# LowFreqSignal_V2.net
KiCad netlist of a schematic drawn in Altium Designer
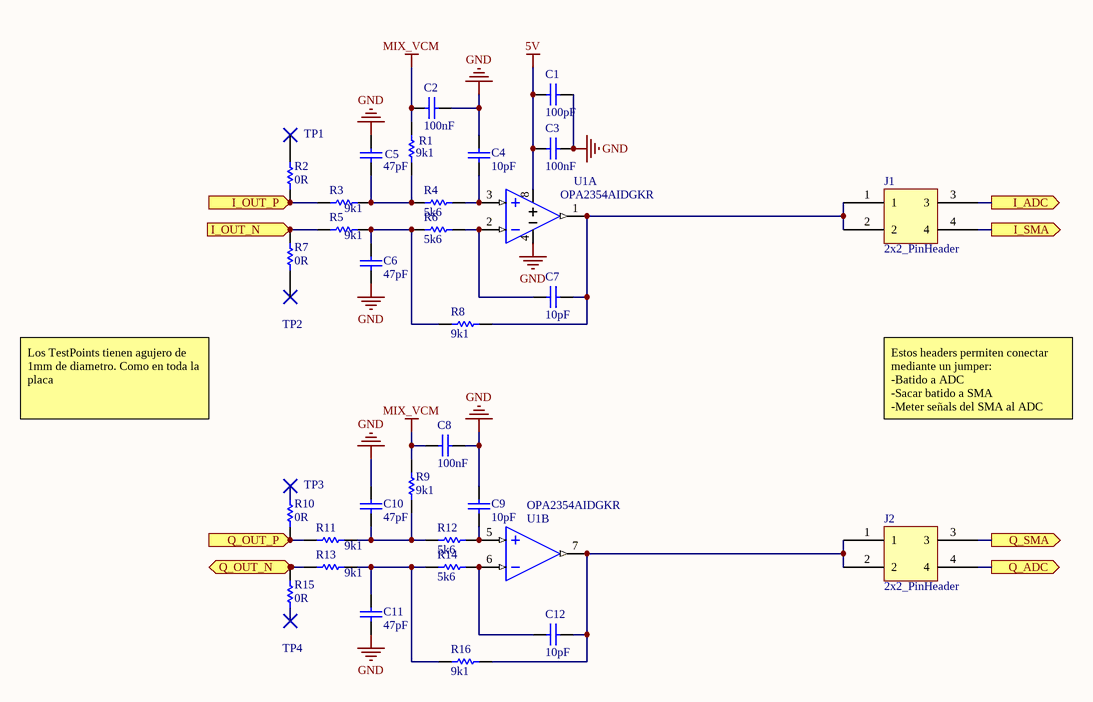
[diagram p0: LowFreqSignal_V2.SchDoc]

(export (version "E")
  (design (tool "Eeschema 10.0.6"))
  (components
    (comp (ref "C1")
      (value "100pF")
      (footprint "0603 Cap")
      (description "CAP CER 100PF 50V X7R 0603")
      (fields
        (field (name "MANUFACTURER") "Samsung Electro-Mechanics America, Inc.")
        (field (name "MANUFACTURER PART NUMBER") "CL10B101KB8NNNC")
      )
      (libsource (lib "Componentes_base") (part "CL10B101KB8NNNC"))
    )
    (comp (ref "C2")
      (value "100nF")
      (footprint "0603 Cap")
      (description "CAP CER 0.1UF 16V X7R 0603")
      (fields
        (field (name "MANUFACTURER") "KEMET")
        (field (name "MANUFACTURER PART NUMBER") "C0603C104K4RACTU")
      )
      (libsource (lib "Componentes_base") (part "C0603C104K4RACTU"))
    )
    (comp (ref "C3")
      (value "100nF")
      (footprint "0603 Cap")
      (description "CAP CER 0.1UF 16V X7R 0603")
      (fields
        (field (name "MANUFACTURER") "KEMET")
        (field (name "MANUFACTURER PART NUMBER") "C0603C104K4RACTU")
      )
      (libsource (lib "Componentes_base") (part "C0603C104K4RACTU"))
    )
    (comp (ref "C4")
      (value "10pF")
      (footprint "0603 Cap")
      (description "CAP CER 16V X7R 0603")
      (fields (field (name "TOLERANCE") "10") (field (name "VOLTAGE") "16"))
      (libsource (lib "Componentes_base") (part "C_0603"))
    )
    (comp (ref "C5")
      (value "47pF")
      (footprint "0603 Cap")
      (description "CAP CER 16V X7R 0603")
      (fields (field (name "TOLERANCE") "10") (field (name "VOLTAGE") "16"))
      (libsource (lib "Componentes_base") (part "C_0603"))
    )
    (comp (ref "C6")
      (value "47pF")
      (footprint "0603 Cap")
      (description "CAP CER 16V X7R 0603")
      (fields (field (name "TOLERANCE") "10") (field (name "VOLTAGE") "16"))
      (libsource (lib "Componentes_base") (part "C_0603"))
    )
    (comp (ref "C7")
      (value "10pF")
      (footprint "0603 Cap")
      (description "CAP CER 16V X7R 0603")
      (fields (field (name "TOLERANCE") "10") (field (name "VOLTAGE") "16"))
      (libsource (lib "Componentes_base") (part "C_0603"))
    )
    (comp (ref "C8")
      (value "100nF")
      (footprint "0603 Cap")
      (description "CAP CER 0.1UF 16V X7R 0603")
      (fields
        (field (name "MANUFACTURER") "KEMET")
        (field (name "MANUFACTURER PART NUMBER") "C0603C104K4RACTU")
      )
      (libsource (lib "Componentes_base") (part "C0603C104K4RACTU"))
    )
    (comp (ref "C9")
      (value "10pF")
      (footprint "0603 Cap")
      (description "CAP CER 16V X7R 0603")
      (fields (field (name "TOLERANCE") "10") (field (name "VOLTAGE") "16"))
      (libsource (lib "Componentes_base") (part "C_0603"))
    )
    (comp (ref "C10")
      (value "47pF")
      (footprint "0603 Cap")
      (description "CAP CER 16V X7R 0603")
      (fields (field (name "TOLERANCE") "10") (field (name "VOLTAGE") "16"))
      (libsource (lib "Componentes_base") (part "C_0603"))
    )
    (comp (ref "C11")
      (value "47pF")
      (footprint "0603 Cap")
      (description "CAP CER 16V X7R 0603")
      (fields (field (name "TOLERANCE") "10") (field (name "VOLTAGE") "16"))
      (libsource (lib "Componentes_base") (part "C_0603"))
    )
    (comp (ref "C12")
      (value "10pF")
      (footprint "0603 Cap")
      (description "CAP CER 16V X7R 0603")
      (fields (field (name "TOLERANCE") "10") (field (name "VOLTAGE") "16"))
      (libsource (lib "Componentes_base") (part "C_0603"))
    )
    (comp (ref "J1")
      (value "2x2_PinHeader")
      (footprint "2x2_PinHeader")
      (libsource (lib "Schlib1") (part "2x2_PinHeader"))
    )
    (comp (ref "J2")
      (value "2x2_PinHeader")
      (footprint "2x2_PinHeader")
      (libsource (lib "Schlib1") (part "2x2_PinHeader"))
    )
    (comp (ref "R1")
      (value "9k1")
      (footprint "0603 Res")
      (description "SMD Resistor, 1%, 0.1W, 0603")
      (fields (field (name "TOLERANCE") "1"))
      (libsource (lib "Componentes_base") (part "R_0603"))
    )
    (comp (ref "R2")
      (value "0R")
      (footprint "0603 Res")
      (description "SMD Resistor, 1%, 0.1W, 0603")
      (fields (field (name "TOLERANCE") "1"))
      (libsource (lib "Componentes_base") (part "R_0603"))
    )
    (comp (ref "R3")
      (value "9k1")
      (footprint "0603 Res")
      (description "SMD Resistor, 1%, 0.1W, 0603")
      (fields (field (name "TOLERANCE") "1"))
      (libsource (lib "Componentes_base") (part "R_0603"))
    )
    (comp (ref "R4")
      (value "5k6")
      (footprint "0603 Res")
      (description "SMD Resistor, 1%, 0.1W, 0603")
      (fields (field (name "TOLERANCE") "1"))
      (libsource (lib "Componentes_base") (part "R_0603"))
    )
    (comp (ref "R5")
      (value "9k1")
      (footprint "0603 Res")
      (description "SMD Resistor, 1%, 0.1W, 0603")
      (fields (field (name "TOLERANCE") "1"))
      (libsource (lib "Componentes_base") (part "R_0603"))
    )
    (comp (ref "R6")
      (value "5k6")
      (footprint "0603 Res")
      (description "SMD Resistor, 1%, 0.1W, 0603")
      (fields (field (name "TOLERANCE") "1"))
      (libsource (lib "Componentes_base") (part "R_0603"))
    )
    (comp (ref "R7")
      (value "0R")
      (footprint "0603 Res")
      (description "SMD Resistor, 1%, 0.1W, 0603")
      (fields (field (name "TOLERANCE") "1"))
      (libsource (lib "Componentes_base") (part "R_0603"))
    )
    (comp (ref "R8")
      (value "9k1")
      (footprint "0603 Res")
      (description "SMD Resistor, 1%, 0.1W, 0603")
      (fields (field (name "TOLERANCE") "1"))
      (libsource (lib "Componentes_base") (part "R_0603"))
    )
    (comp (ref "R9")
      (value "9k1")
      (footprint "0603 Res")
      (description "SMD Resistor, 1%, 0.1W, 0603")
      (fields (field (name "TOLERANCE") "1"))
      (libsource (lib "Componentes_base") (part "R_0603"))
    )
    (comp (ref "R10")
      (value "0R")
      (footprint "0603 Res")
      (description "SMD Resistor, 1%, 0.1W, 0603")
      (fields (field (name "TOLERANCE") "1"))
      (libsource (lib "Componentes_base") (part "R_0603"))
    )
    (comp (ref "R11")
      (value "9k1")
      (footprint "0603 Res")
      (description "SMD Resistor, 1%, 0.1W, 0603")
      (fields (field (name "TOLERANCE") "1"))
      (libsource (lib "Componentes_base") (part "R_0603"))
    )
    (comp (ref "R12")
      (value "5k6")
      (footprint "0603 Res")
      (description "SMD Resistor, 1%, 0.1W, 0603")
      (fields (field (name "TOLERANCE") "1"))
      (libsource (lib "Componentes_base") (part "R_0603"))
    )
    (comp (ref "R13")
      (value "9k1")
      (footprint "0603 Res")
      (description "SMD Resistor, 1%, 0.1W, 0603")
      (fields (field (name "TOLERANCE") "1"))
      (libsource (lib "Componentes_base") (part "R_0603"))
    )
    (comp (ref "R14")
      (value "5k6")
      (footprint "0603 Res")
      (description "SMD Resistor, 1%, 0.1W, 0603")
      (fields (field (name "TOLERANCE") "1"))
      (libsource (lib "Componentes_base") (part "R_0603"))
    )
    (comp (ref "R15")
      (value "0R")
      (footprint "0603 Res")
      (description "SMD Resistor, 1%, 0.1W, 0603")
      (fields (field (name "TOLERANCE") "1"))
      (libsource (lib "Componentes_base") (part "R_0603"))
    )
    (comp (ref "R16")
      (value "9k1")
      (footprint "0603 Res")
      (description "SMD Resistor, 1%, 0.1W, 0603")
      (fields (field (name "TOLERANCE") "1"))
      (libsource (lib "Componentes_base") (part "R_0603"))
    )
    (comp (ref "TP1")
      (value "TEST_POINT_PIN")
      (footprint "TESTPOINT")
      (description "Test point for single pin")
      (libsource (lib "Componentes_base") (part "TEST_POINT_PIN"))
    )
    (comp (ref "TP2")
      (value "TEST_POINT_PIN")
      (footprint "TESTPOINT")
      (description "Test point for single pin")
      (libsource (lib "Componentes_base") (part "TEST_POINT_PIN"))
    )
    (comp (ref "TP3")
      (value "TEST_POINT_PIN")
      (footprint "TESTPOINT")
      (description "Test point for single pin")
      (libsource (lib "Componentes_base") (part "TEST_POINT_PIN"))
    )
    (comp (ref "TP4")
      (value "TEST_POINT_PIN")
      (footprint "TESTPOINT")
      (description "Test point for single pin")
      (libsource (lib "Componentes_base") (part "TEST_POINT_PIN"))
    )
    (comp (ref "U1")
      (value "OPA2354AIDGKR")
      (footprint "MSOP-8")
      (description "IC OPAMP VFB 100MHZ RRO 8VSSOP")
      (fields (field (name "MANUFACTURER") "Texas Instruments"))
      (libsource (lib "Componentes_base") (part "OPA2354AIDGKR"))
    )
  )
  (nets
    (net (code "1") (name "/I_ADC") (class "Default")
      (node (ref "J1") (pin "3") (pinfunction "3_3") (pintype "passive"))
    )
    (net (code "2") (name "/I_OUT_N") (class "Default")
      (node (ref "R5") (pin "2") (pinfunction "2_2") (pintype "passive"))
      (node (ref "R7") (pin "2") (pinfunction "2_2") (pintype "passive"))
    )
    (net (code "3") (name "/I_OUT_P") (class "Default")
      (node (ref "R2") (pin "2") (pinfunction "2_2") (pintype "passive"))
      (node (ref "R3") (pin "1") (pinfunction "1_1") (pintype "passive"))
    )
    (net (code "4") (name "/I_SMA") (class "Default")
      (node (ref "J1") (pin "4") (pinfunction "4_4") (pintype "passive"))
    )
    (net (code "5") (name "/Q_ADC") (class "Default")
      (node (ref "J2") (pin "4") (pinfunction "4_4") (pintype "passive"))
    )
    (net (code "6") (name "/Q_OUT_N") (class "Default")
      (node (ref "R13") (pin "2") (pinfunction "2_2") (pintype "passive"))
      (node (ref "R15") (pin "2") (pinfunction "2_2") (pintype "passive"))
    )
    (net (code "7") (name "/Q_OUT_P") (class "Default")
      (node (ref "R10") (pin "2") (pinfunction "2_2") (pintype "passive"))
      (node (ref "R11") (pin "2") (pinfunction "2_2") (pintype "passive"))
    )
    (net (code "8") (name "/Q_SMA") (class "Default")
      (node (ref "J2") (pin "3") (pinfunction "3_3") (pintype "passive"))
    )
    (net (code "9") (name "5V") (class "Default")
      (node (ref "C1") (pin "1") (pinfunction "1_1") (pintype "passive"))
      (node (ref "C3") (pin "1") (pinfunction "1_1") (pintype "passive"))
      (node (ref "U1") (pin "8") (pinfunction "V+_8") (pintype "power_in"))
    )
    (net (code "10") (name "GND") (class "Default")
      (node (ref "C1") (pin "2") (pinfunction "2_2") (pintype "passive"))
      (node (ref "C10") (pin "2") (pinfunction "2_2") (pintype "passive"))
      (node (ref "C11") (pin "1") (pinfunction "1_1") (pintype "passive"))
      (node (ref "C2") (pin "2") (pinfunction "2_2") (pintype "passive"))
      (node (ref "C3") (pin "2") (pinfunction "2_2") (pintype "passive"))
      (node (ref "C4") (pin "2") (pinfunction "2_2") (pintype "passive"))
      (node (ref "C5") (pin "2") (pinfunction "2_2") (pintype "passive"))
      (node (ref "C6") (pin "1") (pinfunction "1_1") (pintype "passive"))
      (node (ref "C8") (pin "2") (pinfunction "2_2") (pintype "passive"))
      (node (ref "C9") (pin "2") (pinfunction "2_2") (pintype "passive"))
      (node (ref "U1") (pin "4") (pinfunction "V-_4") (pintype "power_in"))
    )
    (net (code "11") (name "MIX_VCM") (class "Default")
      (node (ref "C2") (pin "1") (pinfunction "1_1") (pintype "passive"))
      (node (ref "C8") (pin "1") (pinfunction "1_1") (pintype "passive"))
      (node (ref "R1") (pin "1") (pinfunction "1_1") (pintype "passive"))
      (node (ref "R9") (pin "1") (pinfunction "1_1") (pintype "passive"))
    )
    (net (code "12") (name "Net-(C5-Pad1)") (class "Default")
      (node (ref "C5") (pin "1") (pinfunction "1_1") (pintype "passive"))
      (node (ref "R1") (pin "2") (pinfunction "2_2") (pintype "passive"))
      (node (ref "R3") (pin "2") (pinfunction "2_2") (pintype "passive"))
      (node (ref "R4") (pin "2") (pinfunction "2_2") (pintype "passive"))
    )
    (net (code "13") (name "Net-(C6-Pad2)") (class "Default")
      (node (ref "C6") (pin "2") (pinfunction "2_2") (pintype "passive"))
      (node (ref "R5") (pin "1") (pinfunction "1_1") (pintype "passive"))
      (node (ref "R6") (pin "2") (pinfunction "2_2") (pintype "passive"))
      (node (ref "R8") (pin "2") (pinfunction "2_2") (pintype "passive"))
    )
    (net (code "14") (name "Net-(C10-Pad1)") (class "Default")
      (node (ref "C10") (pin "1") (pinfunction "1_1") (pintype "passive"))
      (node (ref "R11") (pin "1") (pinfunction "1_1") (pintype "passive"))
      (node (ref "R12") (pin "2") (pinfunction "2_2") (pintype "passive"))
      (node (ref "R9") (pin "2") (pinfunction "2_2") (pintype "passive"))
    )
    (net (code "15") (name "Net-(C11-Pad2)") (class "Default")
      (node (ref "C11") (pin "2") (pinfunction "2_2") (pintype "passive"))
      (node (ref "R13") (pin "1") (pinfunction "1_1") (pintype "passive"))
      (node (ref "R14") (pin "2") (pinfunction "2_2") (pintype "passive"))
      (node (ref "R16") (pin "2") (pinfunction "2_2") (pintype "passive"))
    )
    (net (code "16") (name "Net-(R2-Pad1)") (class "Default")
      (node (ref "R2") (pin "1") (pinfunction "1_1") (pintype "passive"))
      (node (ref "TP1") (pin "1") (pinfunction "1_1") (pintype "passive"))
    )
    (net (code "17") (name "Net-(R7-Pad1)") (class "Default")
      (node (ref "R7") (pin "1") (pinfunction "1_1") (pintype "passive"))
      (node (ref "TP2") (pin "1") (pinfunction "1_1") (pintype "passive"))
    )
    (net (code "18") (name "Net-(R10-Pad1)") (class "Default")
      (node (ref "R10") (pin "1") (pinfunction "1_1") (pintype "passive"))
      (node (ref "TP3") (pin "1") (pinfunction "1_1") (pintype "passive"))
    )
    (net (code "19") (name "Net-(R15-Pad1)") (class "Default")
      (node (ref "R15") (pin "1") (pinfunction "1_1") (pintype "passive"))
      (node (ref "TP4") (pin "1") (pinfunction "1_1") (pintype "passive"))
    )
    (net (code "20") (name "Net-(U1A-IN+A)") (class "Default")
      (node (ref "C4") (pin "1") (pinfunction "1_1") (pintype "passive"))
      (node (ref "R4") (pin "1") (pinfunction "1_1") (pintype "passive"))
      (node (ref "U1") (pin "3") (pinfunction "IN+A_3") (pintype "input"))
    )
    (net (code "21") (name "Net-(U1A-IN-A)") (class "Default")
      (node (ref "C7") (pin "1") (pinfunction "1_1") (pintype "passive"))
      (node (ref "R6") (pin "1") (pinfunction "1_1") (pintype "passive"))
      (node (ref "U1") (pin "2") (pinfunction "IN-A_2") (pintype "input"))
    )
    (net (code "22") (name "Net-(U1A-OUTA)") (class "Default")
      (node (ref "C7") (pin "2") (pinfunction "2_2") (pintype "passive"))
      (node (ref "J1") (pin "1") (pinfunction "1_1") (pintype "passive"))
      (node (ref "J1") (pin "2") (pinfunction "2_2") (pintype "passive"))
      (node (ref "R8") (pin "1") (pinfunction "1_1") (pintype "passive"))
      (node (ref "U1") (pin "1") (pinfunction "OUTA_1") (pintype "output"))
    )
    (net (code "23") (name "Net-(U1B-IN+B)") (class "Default")
      (node (ref "C9") (pin "1") (pinfunction "1_1") (pintype "passive"))
      (node (ref "R12") (pin "1") (pinfunction "1_1") (pintype "passive"))
      (node (ref "U1") (pin "5") (pinfunction "IN+B_5") (pintype "input"))
    )
    (net (code "24") (name "Net-(U1B-IN-B)") (class "Default")
      (node (ref "C12") (pin "1") (pinfunction "1_1") (pintype "passive"))
      (node (ref "R14") (pin "1") (pinfunction "1_1") (pintype "passive"))
      (node (ref "U1") (pin "6") (pinfunction "IN-B_6") (pintype "input"))
    )
    (net (code "25") (name "Net-(U1B-OUTB)") (class "Default")
      (node (ref "C12") (pin "2") (pinfunction "2_2") (pintype "passive"))
      (node (ref "J2") (pin "1") (pinfunction "1_1") (pintype "passive"))
      (node (ref "J2") (pin "2") (pinfunction "2_2") (pintype "passive"))
      (node (ref "R16") (pin "1") (pinfunction "1_1") (pintype "passive"))
      (node (ref "U1") (pin "7") (pinfunction "OUTB_7") (pintype "output"))
    )
  )
)
